# PIPCB.net
KiCad netlist of a schematic drawn in EAGLE
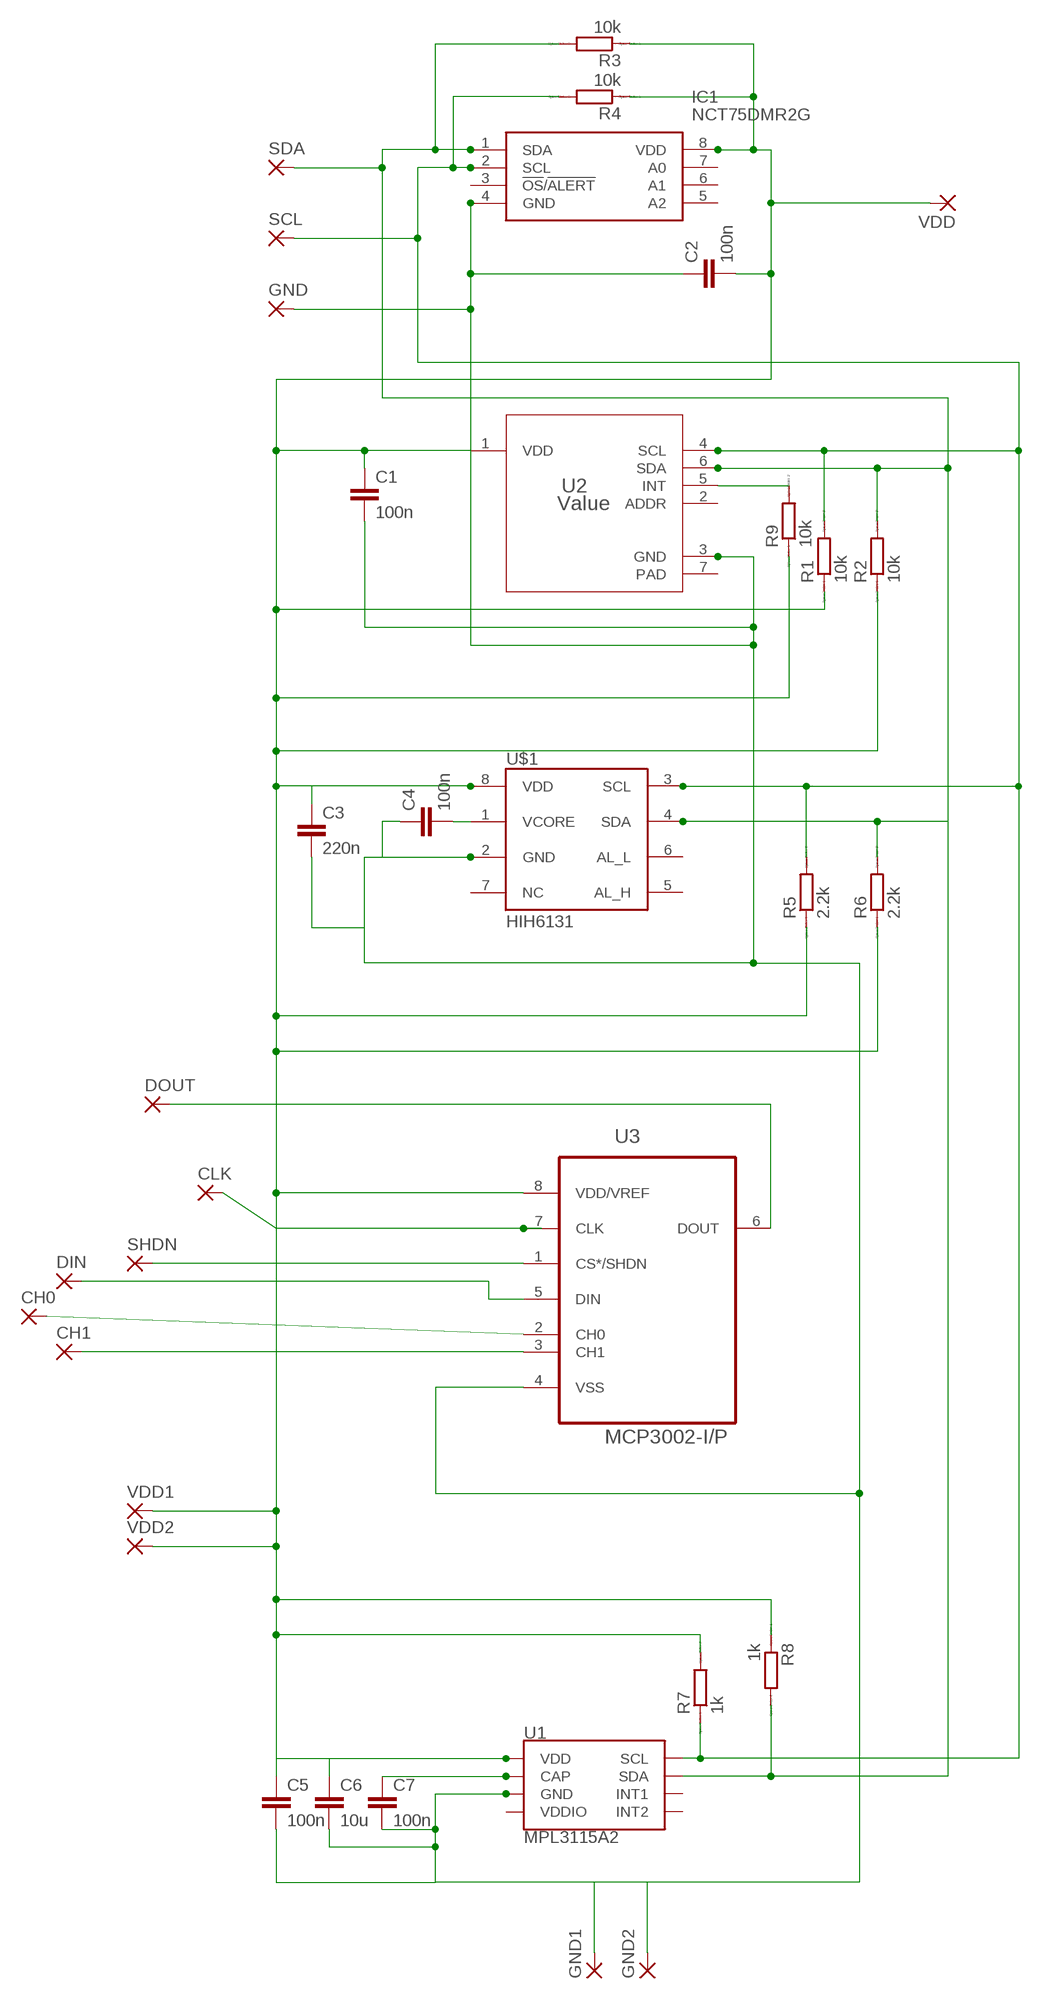
[diagram p0: schematic, sheet 1]

(export (version "E")
  (design (tool "Eeschema 10.0.6"))
  (components
    (comp (ref "C1")
      (value "100n")
      (footprint "eagle-import:C2.5-3")
      (libsource (lib "eagle-import") (part "C2,5-3"))
    )
    (comp (ref "C2")
      (value "100n")
      (footprint "eagle-import:C2.5-3")
      (libsource (lib "eagle-import") (part "C2,5-3"))
    )
    (comp (ref "C3")
      (value "220n")
      (footprint "eagle-import:C2.5-3")
      (libsource (lib "eagle-import") (part "C2,5-3"))
    )
    (comp (ref "C4")
      (value "100n")
      (footprint "eagle-import:C2.5-3")
      (libsource (lib "eagle-import") (part "C2,5-3"))
    )
    (comp (ref "C5")
      (value "100n")
      (footprint "eagle-import:C2.5-3")
      (libsource (lib "eagle-import") (part "C2,5-3"))
    )
    (comp (ref "C6")
      (value "10u")
      (footprint "eagle-import:C2.5-3")
      (libsource (lib "eagle-import") (part "C2,5-3"))
    )
    (comp (ref "C7")
      (value "100n")
      (footprint "eagle-import:C2.5-3")
      (libsource (lib "eagle-import") (part "C2,5-3"))
    )
    (comp (ref "CH0")
      (value "2,54/0,8")
      (footprint "eagle-import:2,54_0,8")
      (libsource (lib "eagle-import") (part "2,54/0,8"))
    )
    (comp (ref "CH1")
      (value "2,54/0,8")
      (footprint "eagle-import:2,54_0,8")
      (libsource (lib "eagle-import") (part "2,54/0,8"))
    )
    (comp (ref "CLK")
      (value "2,54/0,8")
      (footprint "eagle-import:2,54_0,8")
      (libsource (lib "eagle-import") (part "2,54/0,8"))
    )
    (comp (ref "DIN")
      (value "2,54/0,8")
      (footprint "eagle-import:2,54_0,8")
      (libsource (lib "eagle-import") (part "2,54/0,8"))
    )
    (comp (ref "DOUT")
      (value "2,54/0,8")
      (footprint "eagle-import:2,54_0,8")
      (libsource (lib "eagle-import") (part "2,54/0,8"))
    )
    (comp (ref "GND")
      (value "2,54/0,8")
      (footprint "eagle-import:2,54_0,8")
      (libsource (lib "eagle-import") (part "2,54/0,8"))
    )
    (comp (ref "GND1")
      (value "2,54/0,8")
      (footprint "eagle-import:2,54_0,8")
      (libsource (lib "eagle-import") (part "2,54/0,8"))
    )
    (comp (ref "GND2")
      (value "2,54/0,8")
      (footprint "eagle-import:2,54_0,8")
      (libsource (lib "eagle-import") (part "2,54/0,8"))
    )
    (comp (ref "IC1")
      (value "NCT75DMR2G")
      (footprint "eagle-import:SOP65P490X110-8N")
      (fields (field (name "RS_PART_NUMBER") "8064942"))
      (libsource (lib "eagle-import") (part "NCT75DMR2G"))
    )
    (comp (ref "R1")
      (value "10k")
      (footprint "eagle-import:0207_10")
      (libsource (lib "eagle-import") (part "R0207/10"))
    )
    (comp (ref "R2")
      (value "10k")
      (footprint "eagle-import:0207_10")
      (libsource (lib "eagle-import") (part "R0207/10"))
    )
    (comp (ref "R3")
      (value "10k")
      (footprint "eagle-import:0207_10")
      (libsource (lib "eagle-import") (part "R0207/10"))
    )
    (comp (ref "R4")
      (value "10k")
      (footprint "eagle-import:0207_10")
      (libsource (lib "eagle-import") (part "R0207/10"))
    )
    (comp (ref "R5")
      (value "2.2k")
      (footprint "eagle-import:0207_10")
      (libsource (lib "eagle-import") (part "R0207/10"))
    )
    (comp (ref "R6")
      (value "2.2k")
      (footprint "eagle-import:0207_10")
      (libsource (lib "eagle-import") (part "R0207/10"))
    )
    (comp (ref "R7")
      (value "1k")
      (footprint "eagle-import:0207_10")
      (libsource (lib "eagle-import") (part "R0207/10"))
    )
    (comp (ref "R8")
      (value "1k")
      (footprint "eagle-import:0207_10")
      (libsource (lib "eagle-import") (part "R0207/10"))
    )
    (comp (ref "R9")
      (value "10k")
      (footprint "eagle-import:0207_10")
      (libsource (lib "eagle-import") (part "R0207/10"))
    )
    (comp (ref "SCL")
      (value "2,54/0,8")
      (footprint "eagle-import:2,54_0,8")
      (libsource (lib "eagle-import") (part "2,54/0,8"))
    )
    (comp (ref "SDA")
      (value "2,54/0,8")
      (footprint "eagle-import:2,54_0,8")
      (libsource (lib "eagle-import") (part "2,54/0,8"))
    )
    (comp (ref "SHDN")
      (value "2,54/0,8")
      (footprint "eagle-import:2,54_0,8")
      (libsource (lib "eagle-import") (part "2,54/0,8"))
    )
    (comp (ref "U$1")
      (value "HIH6131")
      (footprint "eagle-import:SOIC8")
      (libsource (lib "eagle-import") (part "HIH6131"))
    )
    (comp (ref "U1")
      (value "MPL3115A2")
      (footprint "eagle-import:LGA-8-5X3")
      (libsource (lib "eagle-import") (part "MPL3115A2"))
    )
    (comp (ref "U2")
      (value "Value")
      (footprint "eagle-import:DNP0006A")
      (fields (field (name "MANUFACTURER") "Texas Instruments") (field (name "PARTNUMBER") "OPT3001DNP"))
      (libsource (lib "eagle-import") (part "OPT3001DNPR"))
    )
    (comp (ref "U3")
      (value "MCP3002-I/P")
      (footprint "eagle-import:DIP254P762X533-8")
      (libsource (lib "eagle-import") (part "MCP3002-I/P"))
    )
    (comp (ref "VDD")
      (value "2,54/0,8")
      (footprint "eagle-import:2,54_0,8")
      (libsource (lib "eagle-import") (part "2,54/0,8"))
    )
    (comp (ref "VDD1")
      (value "2,54/0,8")
      (footprint "eagle-import:2,54_0,8")
      (libsource (lib "eagle-import") (part "2,54/0,8"))
    )
    (comp (ref "VDD2")
      (value "2,54/0,8")
      (footprint "eagle-import:2,54_0,8")
      (libsource (lib "eagle-import") (part "2,54/0,8"))
    )
  )
  (nets
    (net (code "1") (name "/VDDIO") (class "Default")
      (node (ref "U1") (pin "4") (pinfunction "VDDIO_4") (pintype "power_in"))
    )
    (net (code "2") (name "Net-(CH0-P)") (class "Default")
      (node (ref "CH0") (pin "1") (pinfunction "P_1") (pintype "passive"))
      (node (ref "U3") (pin "2") (pinfunction "CH0_2") (pintype "input"))
    )
    (net (code "3") (name "Net-(CH1-P)") (class "Default")
      (node (ref "CH1") (pin "1") (pinfunction "P_1") (pintype "passive"))
      (node (ref "U3") (pin "3") (pinfunction "CH1_3") (pintype "input"))
    )
    (net (code "4") (name "Net-(CLK-P)") (class "Default")
      (node (ref "CLK") (pin "1") (pinfunction "P_1") (pintype "passive"))
      (node (ref "U3") (pin "7") (pinfunction "CLK_7") (pintype "input"))
    )
    (net (code "5") (name "Net-(DIN-P)") (class "Default")
      (node (ref "DIN") (pin "1") (pinfunction "P_1") (pintype "passive"))
      (node (ref "U3") (pin "5") (pinfunction "DIN_5") (pintype "input"))
    )
    (net (code "6") (name "Net-(DOUT-P)") (class "Default")
      (node (ref "DOUT") (pin "1") (pinfunction "P_1") (pintype "passive"))
      (node (ref "U3") (pin "6") (pinfunction "DOUT_6") (pintype "output"))
    )
    (net (code "7") (name "Net-(GND-P)") (class "Default")
      (node (ref "C1") (pin "2") (pinfunction "2_2") (pintype "passive"))
      (node (ref "C2") (pin "1") (pinfunction "1_1") (pintype "passive"))
      (node (ref "C3") (pin "2") (pinfunction "2_2") (pintype "passive"))
      (node (ref "C4") (pin "1") (pinfunction "1_1") (pintype "passive"))
      (node (ref "C5") (pin "2") (pinfunction "2_2") (pintype "passive"))
      (node (ref "C6") (pin "2") (pinfunction "2_2") (pintype "passive"))
      (node (ref "C7") (pin "2") (pinfunction "2_2") (pintype "passive"))
      (node (ref "GND") (pin "1") (pinfunction "P_1") (pintype "passive"))
      (node (ref "GND1") (pin "1") (pinfunction "P_1") (pintype "passive"))
      (node (ref "GND2") (pin "1") (pinfunction "P_1") (pintype "passive"))
      (node (ref "IC1") (pin "4") (pinfunction "GND_4") (pintype "power_in"))
      (node (ref "U$1") (pin "2") (pinfunction "GND_2") (pintype "bidirectional"))
      (node (ref "U1") (pin "3") (pinfunction "GND_3") (pintype "power_in"))
      (node (ref "U2") (pin "3") (pinfunction "GND_3") (pintype "power_in"))
      (node (ref "U3") (pin "4") (pinfunction "VSS_4") (pintype "passive"))
    )
    (net (code "8") (name "Net-(IC1-SCL)") (class "Default")
      (node (ref "IC1") (pin "2") (pinfunction "SCL_2") (pintype "bidirectional"))
      (node (ref "R1") (pin "2") (pinfunction "2_2") (pintype "passive"))
      (node (ref "R4") (pin "2") (pinfunction "2_2") (pintype "passive"))
      (node (ref "R5") (pin "2") (pinfunction "2_2") (pintype "passive"))
      (node (ref "R7") (pin "1") (pinfunction "1_1") (pintype "passive"))
      (node (ref "SCL") (pin "1") (pinfunction "P_1") (pintype "passive"))
      (node (ref "U$1") (pin "3") (pinfunction "SCL_3") (pintype "bidirectional"))
      (node (ref "U1") (pin "8") (pinfunction "SCL_8") (pintype "bidirectional"))
      (node (ref "U2") (pin "4") (pinfunction "SCL_4") (pintype "input"))
    )
    (net (code "9") (name "Net-(IC1-SDA)") (class "Default")
      (node (ref "IC1") (pin "1") (pinfunction "SDA_1") (pintype "bidirectional"))
      (node (ref "R2") (pin "2") (pinfunction "2_2") (pintype "passive"))
      (node (ref "R3") (pin "2") (pinfunction "2_2") (pintype "passive"))
      (node (ref "R6") (pin "2") (pinfunction "2_2") (pintype "passive"))
      (node (ref "R8") (pin "2") (pinfunction "2_2") (pintype "passive"))
      (node (ref "SDA") (pin "1") (pinfunction "P_1") (pintype "passive"))
      (node (ref "U$1") (pin "4") (pinfunction "SDA_4") (pintype "bidirectional"))
      (node (ref "U1") (pin "7") (pinfunction "SDA_7") (pintype "bidirectional"))
      (node (ref "U2") (pin "6") (pinfunction "SDA_6") (pintype "input"))
    )
    (net (code "10") (name "Net-(IC1-VDD)") (class "Default")
      (node (ref "C1") (pin "1") (pinfunction "1_1") (pintype "passive"))
      (node (ref "C2") (pin "2") (pinfunction "2_2") (pintype "passive"))
      (node (ref "C3") (pin "1") (pinfunction "1_1") (pintype "passive"))
      (node (ref "C5") (pin "1") (pinfunction "1_1") (pintype "passive"))
      (node (ref "C6") (pin "1") (pinfunction "1_1") (pintype "passive"))
      (node (ref "IC1") (pin "8") (pinfunction "VDD_8") (pintype "power_in"))
      (node (ref "R1") (pin "1") (pinfunction "1_1") (pintype "passive"))
      (node (ref "R2") (pin "1") (pinfunction "1_1") (pintype "passive"))
      (node (ref "R3") (pin "1") (pinfunction "1_1") (pintype "passive"))
      (node (ref "R4") (pin "1") (pinfunction "1_1") (pintype "passive"))
      (node (ref "R5") (pin "1") (pinfunction "1_1") (pintype "passive"))
      (node (ref "R6") (pin "1") (pinfunction "1_1") (pintype "passive"))
      (node (ref "R7") (pin "2") (pinfunction "2_2") (pintype "passive"))
      (node (ref "R8") (pin "1") (pinfunction "1_1") (pintype "passive"))
      (node (ref "R9") (pin "1") (pinfunction "1_1") (pintype "passive"))
      (node (ref "U$1") (pin "8") (pinfunction "VDD_8") (pintype "bidirectional"))
      (node (ref "U1") (pin "1") (pinfunction "VDD_1") (pintype "power_in"))
      (node (ref "U2") (pin "1") (pinfunction "VDD_1") (pintype "power_in"))
      (node (ref "U3") (pin "8") (pinfunction "VDD/VREF_8") (pintype "power_in"))
      (node (ref "VDD") (pin "1") (pinfunction "P_1") (pintype "passive"))
      (node (ref "VDD1") (pin "1") (pinfunction "P_1") (pintype "passive"))
      (node (ref "VDD2") (pin "1") (pinfunction "P_1") (pintype "passive"))
    )
    (net (code "11") (name "Net-(SHDN-P)") (class "Default")
      (node (ref "SHDN") (pin "1") (pinfunction "P_1") (pintype "passive"))
      (node (ref "U3") (pin "1") (pinfunction "CS*/SHDN_1") (pintype "input"))
    )
    (net (code "12") (name "Net-(U$1-VCORE)") (class "Default")
      (node (ref "C4") (pin "2") (pinfunction "2_2") (pintype "passive"))
      (node (ref "U$1") (pin "1") (pinfunction "VCORE_1") (pintype "bidirectional"))
    )
    (net (code "13") (name "Net-(U1-CAP)") (class "Default")
      (node (ref "C7") (pin "1") (pinfunction "1_1") (pintype "passive"))
      (node (ref "U1") (pin "2") (pinfunction "CAP_2") (pintype "power_in"))
    )
    (net (code "14") (name "Net-(U2-INT)") (class "Default")
      (node (ref "R9") (pin "2") (pinfunction "2_2") (pintype "passive"))
      (node (ref "U2") (pin "5") (pinfunction "INT_5") (pintype "output"))
    )
    (net (code "15") (name "unconnected-(IC1-A0-Pad7)") (class "Default")
      (node (ref "IC1") (pin "7") (pinfunction "A0_7") (pintype "bidirectional"))
    )
    (net (code "16") (name "unconnected-(IC1-A1-Pad6)") (class "Default")
      (node (ref "IC1") (pin "6") (pinfunction "A1_6") (pintype "bidirectional"))
    )
    (net (code "17") (name "unconnected-(IC1-A2-Pad5)") (class "Default")
      (node (ref "IC1") (pin "5") (pinfunction "A2_5") (pintype "bidirectional"))
    )
    (net (code "18") (name "unconnected-(IC1-~{OS}{slash}~{ALERT}-Pad3)") (class "Default")
      (node (ref "IC1") (pin "3") (pinfunction "~{OS}/~{ALERT}_3") (pintype "bidirectional"))
    )
    (net (code "19") (name "unconnected-(U$1-AL_H-Pad5)") (class "Default")
      (node (ref "U$1") (pin "5") (pinfunction "AL_H_5") (pintype "bidirectional"))
    )
    (net (code "20") (name "unconnected-(U$1-AL_L-Pad6)") (class "Default")
      (node (ref "U$1") (pin "6") (pinfunction "AL_L_6") (pintype "bidirectional"))
    )
    (net (code "21") (name "unconnected-(U$1-NC-Pad7)") (class "Default")
      (node (ref "U$1") (pin "7") (pinfunction "NC_7") (pintype "bidirectional"))
    )
    (net (code "22") (name "unconnected-(U1-INT1-Pad6)") (class "Default")
      (node (ref "U1") (pin "6") (pinfunction "INT1_6") (pintype "output"))
    )
    (net (code "23") (name "unconnected-(U1-INT2-Pad5)") (class "Default")
      (node (ref "U1") (pin "5") (pinfunction "INT2_5") (pintype "output"))
    )
    (net (code "24") (name "unconnected-(U2-ADDR-Pad2)") (class "Default")
      (node (ref "U2") (pin "2") (pinfunction "ADDR_2") (pintype "input"))
    )
    (net (code "25") (name "unconnected-(U2-PAD-Pad7)") (class "Default")
      (node (ref "U2") (pin "7") (pinfunction "PAD_7") (pintype "passive"))
    )
  )
)
